# INVERTER_ALTIUM.net
KiCad netlist of a schematic drawn in Altium Designer
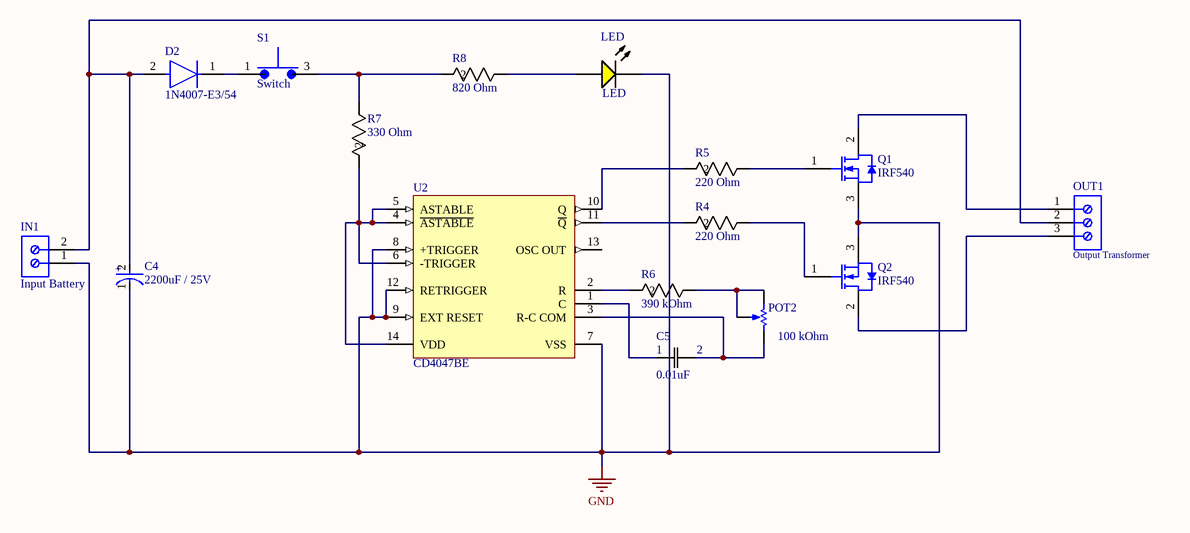
[diagram p0: INVERTER_ALTIUM.SchDoc]

(export (version "E")
  (design (tool "Eeschema 10.0.6"))
  (components
    (comp (ref "C4")
      (value "2200uF / 25V")
      (footprint "FP-RAD-TH-D_16_0_5-L_25_2-MFG")
      (description "Aluminum Electrolytic Capacitors (Radial Lead Type) AEC-Q200 Qualified 2200uF ±20% 25V")
      (fields (field (name "TOLERANCE") "20%") (field (name "VOLTAGE") "25V"))
      (libsource (lib "Altium Content Vault") (part "203bc49f2ac43e59fd269a8c329ed05"))
    )
    (comp (ref "C5")
      (value "0.01uF")
      (footprint "CAP_C315_KEM")
      (description "No Description Available")
      (fields
        (field (name "MANUFACTURER_PART_NUMBER") "C315C103M1U5TA")
        (field (name "COPYRIGHT") "Copyright (C) 2022 Ultra Librarian. All rights reserved.")
      )
      (libsource (lib "10uF") (part "C315C103M1U5TA"))
    )
    (comp (ref "D2")
      (value "1N4007-E3/54")
      (footprint "FP-1N4007-MFG")
      (description "DIODE GEN PURP 1KV 1A DO204AL")
      (fields
        (field (name "OCTOPART") "https://octopart.com/1n4007-e3%2F54-vishay-39548207")
        (field (name "MANUFACTURER") "Vishay")
      )
      (libsource (lib "Altium Content Vault") (part "d7152d700b627762746794eb795d46e"))
    )
    (comp (ref "IN1")
      (value "Input Battery")
      (footprint "691102710002")
      (description "Series 102 - 5.00 mm Horizontal Entry Modular with Pressure Clamp WR-TBL, 2 pin")
      (fields
        (field (name "MANUFACTURER") "Wurth Elektronik")
        (field (name "PART NUMBER") "691102710002")
        (field (name "PUBLISHER") "WurthElektronik")
      )
      (libsource (lib "Altium Content Vault") (part "WE-CN-1P-F-TB2"))
    )
    (comp (ref "LED")
      (value "LED")
      (footprint "KING-WP7113SYD_V")
      (description "The Super Bright Yellow Device, 2 V, -40 to 85 degC, 2-Pin THD, RoHS, Tape and Reel")
      (fields (field (name "TOLERANCE") "1%"))
      (libsource (lib "Altium Content Vault") (part "LED-YELLOW-AK-2"))
    )
    (comp (ref "OUT1")
      (value "Output Transformer")
      (footprint "691102710003")
      (description "Series 102 - 5.00 mm Horizontal Entry Modular with Pressure Clamp WR-TBL, 3 pin")
      (fields
        (field (name "MANUFACTURER") "Wurth Elektronik")
        (field (name "PART NUMBER") "691102710003")
        (field (name "PUBLISHER") "WurthElektronik")
      )
      (libsource (lib "Altium Content Vault") (part "WE-CN-1P-F-TB3"))
    )
    (comp (ref "POT2")
      (value "100 kOhm")
      (footprint "BOUR-3362P")
      (description "Square Trimpot(R) Trimming Potentiometer, 10 KOhm, 300 V, -55 to 125 degC, 3-Pin THD, RoHS, Tube")
      (fields (field (name "TOLERANCE") "1%"))
      (libsource (lib "Altium Content Vault") (part "RES-POT-3"))
    )
    (comp (ref "Q1")
      (value "IRF540")
      (footprint "NXP-SOT78A")
      (description "N-Channel TrenchMOS Logic Level FET, 100 V, 46 A, 3-Pin SOT78A, Rail")
      (fields
        (field (name "MANUFACTURER") "NXP Semiconductors")
        (field (name "PARTNUMBER") "BUK9529-100B,127")
      )
      (libsource (lib "Altium Content Vault") (part "NXP-NMOS-GDS-3"))
    )
    (comp (ref "Q2")
      (value "IRF540")
      (footprint "NXP-SOT78A")
      (description "N-Channel TrenchMOS Logic Level FET, 100 V, 46 A, 3-Pin SOT78A, Rail")
      (fields
        (field (name "MANUFACTURER") "NXP Semiconductors")
        (field (name "PARTNUMBER") "BUK9529-100B,127")
      )
      (libsource (lib "Altium Content Vault") (part "NXP-NMOS-GDS-3"))
    )
    (comp (ref "R4")
      (value "220 Ohm")
      (footprint "RES_PRO1")
      (description "No Description Available")
      (fields
        (field (name "MANUFACTURER_PART_NUMBER") "PR01000101001JA100")
        (field (name "COPYRIGHT") "Copyright (C) 2022 Ultra Librarian. All rights reserved.")
      )
      (libsource (lib "Resistor") (part "PR01000101001JA100"))
    )
    (comp (ref "R5")
      (value "220 Ohm")
      (footprint "RES_PRO1")
      (description "No Description Available")
      (fields
        (field (name "MANUFACTURER_PART_NUMBER") "PR01000101001JA100")
        (field (name "COPYRIGHT") "Copyright (C) 2022 Ultra Librarian. All rights reserved.")
      )
      (libsource (lib "Resistor") (part "PR01000101001JA100"))
    )
    (comp (ref "R6")
      (value "390 kOhm")
      (footprint "RES_PRO1")
      (description "No Description Available")
      (fields
        (field (name "MANUFACTURER_PART_NUMBER") "PR01000101001JA100")
        (field (name "COPYRIGHT") "Copyright (C) 2022 Ultra Librarian. All rights reserved.")
      )
      (libsource (lib "Resistor") (part "PR01000101001JA100"))
    )
    (comp (ref "R7")
      (value "330 Ohm")
      (footprint "RES_PRO1")
      (description "No Description Available")
      (fields
        (field (name "MANUFACTURER_PART_NUMBER") "PR01000101001JA100")
        (field (name "COPYRIGHT") "Copyright (C) 2022 Ultra Librarian. All rights reserved.")
      )
      (libsource (lib "Resistor") (part "PR01000101001JA100"))
    )
    (comp (ref "R8")
      (value "820 Ohm")
      (footprint "RES_PRO1")
      (description "No Description Available")
      (fields
        (field (name "MANUFACTURER_PART_NUMBER") "PR01000101001JA100")
        (field (name "COPYRIGHT") "Copyright (C) 2022 Ultra Librarian. All rights reserved.")
      )
      (libsource (lib "Resistor") (part "PR01000101001JA100"))
    )
    (comp (ref "S1")
      (value "Switch")
      (footprint "SW_PMS9P1B10M2QE")
      (description "Pushbutton Switch SPST-NO Standard Through Hole")
      (fields (field (name "MP") "PMS9P1B10M2QE") (field (name "MF") "TE Connectivity ALCOSWITCH Switches"))
      (libsource (lib "PMS9P1B10M2QE") (part "PMS9P1B10M2QE"))
    )
    (comp (ref "U2")
      (value "CD4047BE")
      (footprint "N0014A")
      (description "CMOS Low-Power Monostable/Astable Multivibrator, N0014A, TUBE")
      (fields
        (field (name "MANUFACTURER") "Texas Instruments")
        (field (name "GENERIC PART NUMBER") "CD4047B")
      )
      (libsource (lib "Altium Content Vault") (part "TI-CD4047B-14"))
    )
  )
  (nets
    (net (code "1") (name "GND") (class "Default")
      (node (ref "C4") (pin "1") (pinfunction "C_1") (pintype "passive"))
      (node (ref "IN1") (pin "1") (pinfunction "1_1") (pintype "passive"))
      (node (ref "LED") (pin "2") (pinfunction "K_2") (pintype "passive"))
      (node (ref "Q1") (pin "3") (pinfunction "S_3") (pintype "passive"))
      (node (ref "Q2") (pin "3") (pinfunction "S_3") (pintype "passive"))
      (node (ref "U2") (pin "12") (pinfunction "RETRIGGER_12") (pintype "input"))
      (node (ref "U2") (pin "7") (pinfunction "VSS_7") (pintype "power_in"))
      (node (ref "U2") (pin "8") (pinfunction "+TRIGGER_8") (pintype "input"))
      (node (ref "U2") (pin "9") (pinfunction "EXT_RESET_9") (pintype "input"))
    )
    (net (code "2") (name "Net-(C4-A)") (class "Default")
      (node (ref "C4") (pin "2") (pinfunction "A_2") (pintype "passive"))
      (node (ref "D2") (pin "2") (pinfunction "A_2") (pintype "passive"))
      (node (ref "IN1") (pin "2") (pinfunction "2_2") (pintype "passive"))
      (node (ref "OUT1") (pin "2") (pinfunction "2_2") (pintype "passive"))
    )
    (net (code "3") (name "Net-(D2-C)") (class "Default")
      (node (ref "D2") (pin "1") (pinfunction "C_1") (pintype "passive"))
      (node (ref "S1") (pin "1") (pinfunction "1_1") (pintype "passive"))
    )
    (net (code "4") (name "Net-(LED-A)") (class "Default")
      (node (ref "LED") (pin "1") (pinfunction "A_1") (pintype "passive"))
      (node (ref "R8") (pin "1") (pinfunction "1_1") (pintype "passive"))
    )
    (net (code "5") (name "Net-(POT2-CCW)") (class "Default")
      (node (ref "C5") (pin "2") (pinfunction "2_2") (pintype "passive"))
      (node (ref "POT2") (pin "1") (pinfunction "CCW_1") (pintype "passive"))
      (node (ref "U2") (pin "3") (pinfunction "R-C_COM_3") (pintype "passive"))
    )
    (net (code "6") (name "Net-(POT2-CW)") (class "Default")
      (node (ref "POT2") (pin "2") (pinfunction "S_2") (pintype "passive"))
      (node (ref "POT2") (pin "3") (pinfunction "CW_3") (pintype "passive"))
      (node (ref "R6") (pin "1") (pinfunction "1_1") (pintype "passive"))
    )
    (net (code "7") (name "Net-(Q1-D)") (class "Default")
      (node (ref "OUT1") (pin "1") (pinfunction "1_1") (pintype "passive"))
      (node (ref "Q1") (pin "2") (pinfunction "D_2") (pintype "passive"))
    )
    (net (code "8") (name "Net-(Q1-G)") (class "Default")
      (node (ref "Q1") (pin "1") (pinfunction "G_1") (pintype "passive"))
      (node (ref "R5") (pin "1") (pinfunction "1_1") (pintype "passive"))
    )
    (net (code "9") (name "Net-(Q2-D)") (class "Default")
      (node (ref "OUT1") (pin "3") (pinfunction "3_3") (pintype "passive"))
      (node (ref "Q2") (pin "2") (pinfunction "D_2") (pintype "passive"))
    )
    (net (code "10") (name "Net-(Q2-G)") (class "Default")
      (node (ref "Q2") (pin "1") (pinfunction "G_1") (pintype "passive"))
      (node (ref "R4") (pin "1") (pinfunction "1_1") (pintype "passive"))
    )
    (net (code "11") (name "Net-(R7-Pad1)") (class "Default")
      (node (ref "R7") (pin "1") (pinfunction "1_1") (pintype "passive"))
      (node (ref "R8") (pin "2") (pinfunction "2_2") (pintype "passive"))
      (node (ref "S1") (pin "3") (pinfunction "3_3") (pintype "passive"))
    )
    (net (code "12") (name "Net-(U2--TRIGGER)") (class "Default")
      (node (ref "R7") (pin "2") (pinfunction "2_2") (pintype "passive"))
      (node (ref "U2") (pin "14") (pinfunction "VDD_14") (pintype "power_in"))
      (node (ref "U2") (pin "4") (pinfunction "~{ASTABLE}_4") (pintype "input"))
      (node (ref "U2") (pin "5") (pinfunction "ASTABLE_5") (pintype "input"))
      (node (ref "U2") (pin "6") (pinfunction "-TRIGGER_6") (pintype "input"))
    )
    (net (code "13") (name "Net-(U2-C)") (class "Default")
      (node (ref "C5") (pin "1") (pinfunction "1_1") (pintype "passive"))
      (node (ref "U2") (pin "1") (pinfunction "C_1") (pintype "passive"))
    )
    (net (code "14") (name "Net-(U2-Q)") (class "Default")
      (node (ref "R5") (pin "2") (pinfunction "2_2") (pintype "passive"))
      (node (ref "U2") (pin "10") (pinfunction "Q_10") (pintype "output"))
    )
    (net (code "15") (name "Net-(U2-R)") (class "Default")
      (node (ref "R6") (pin "2") (pinfunction "2_2") (pintype "passive"))
      (node (ref "U2") (pin "2") (pinfunction "R_2") (pintype "passive"))
    )
    (net (code "16") (name "Net-(U2-~{Q})") (class "Default")
      (node (ref "R4") (pin "2") (pinfunction "2_2") (pintype "passive"))
      (node (ref "U2") (pin "11") (pinfunction "~{Q}_11") (pintype "output"))
    )
    (net (code "17") (name "unconnected-(U2-OSC_OUT-Pad13)") (class "Default")
      (node (ref "U2") (pin "13") (pinfunction "OSC_OUT_13") (pintype "output"))
    )
  )
)
